# heart-shaped-smd-light-gift.net
KiCad netlist of a schematic drawn in EAGLE
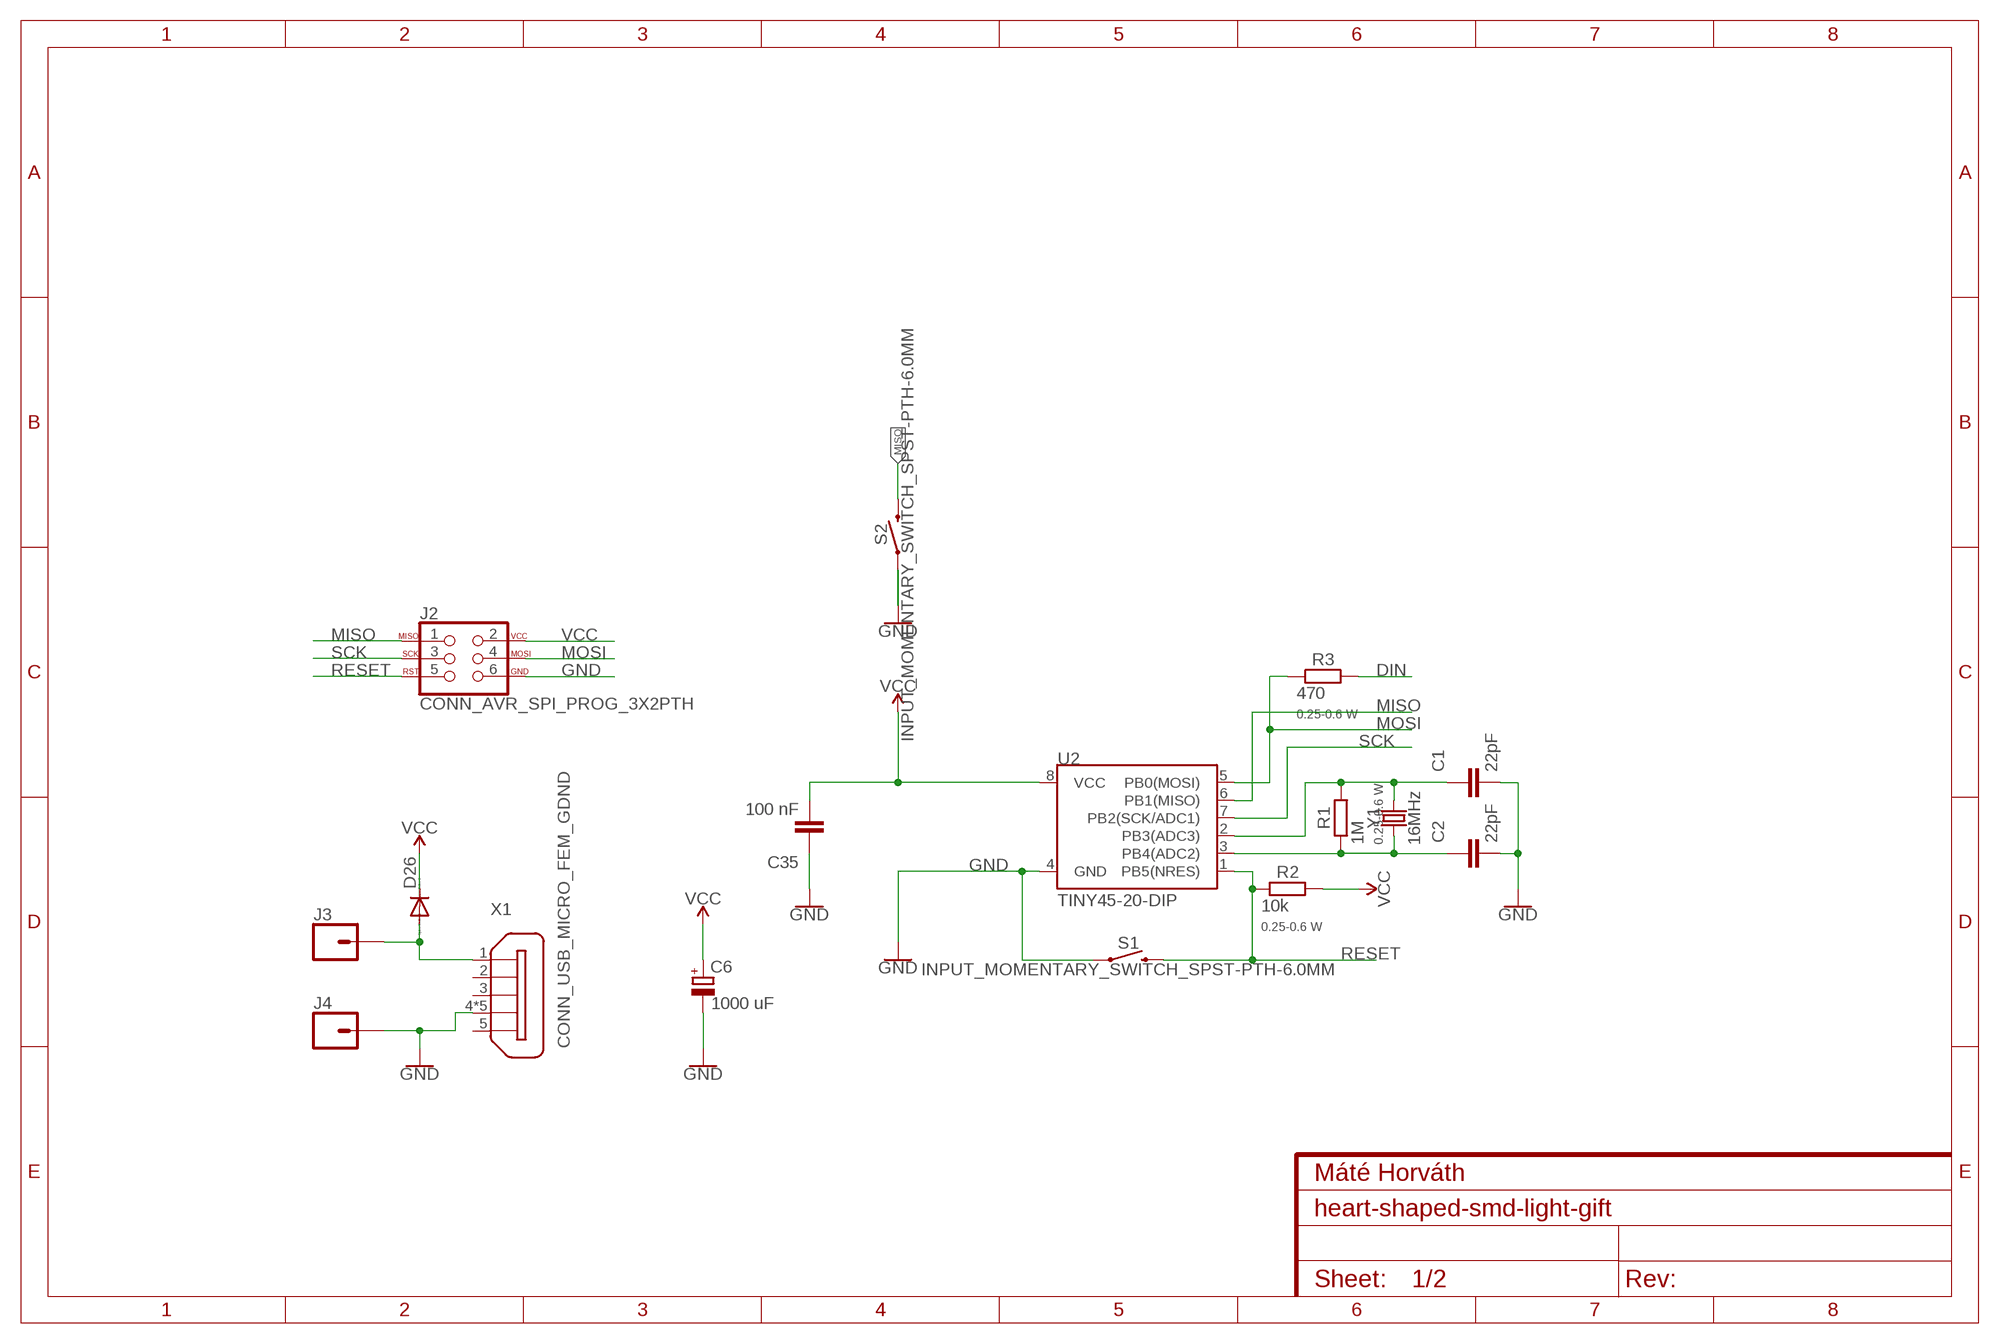
[diagram p0: schematic, sheet 1]
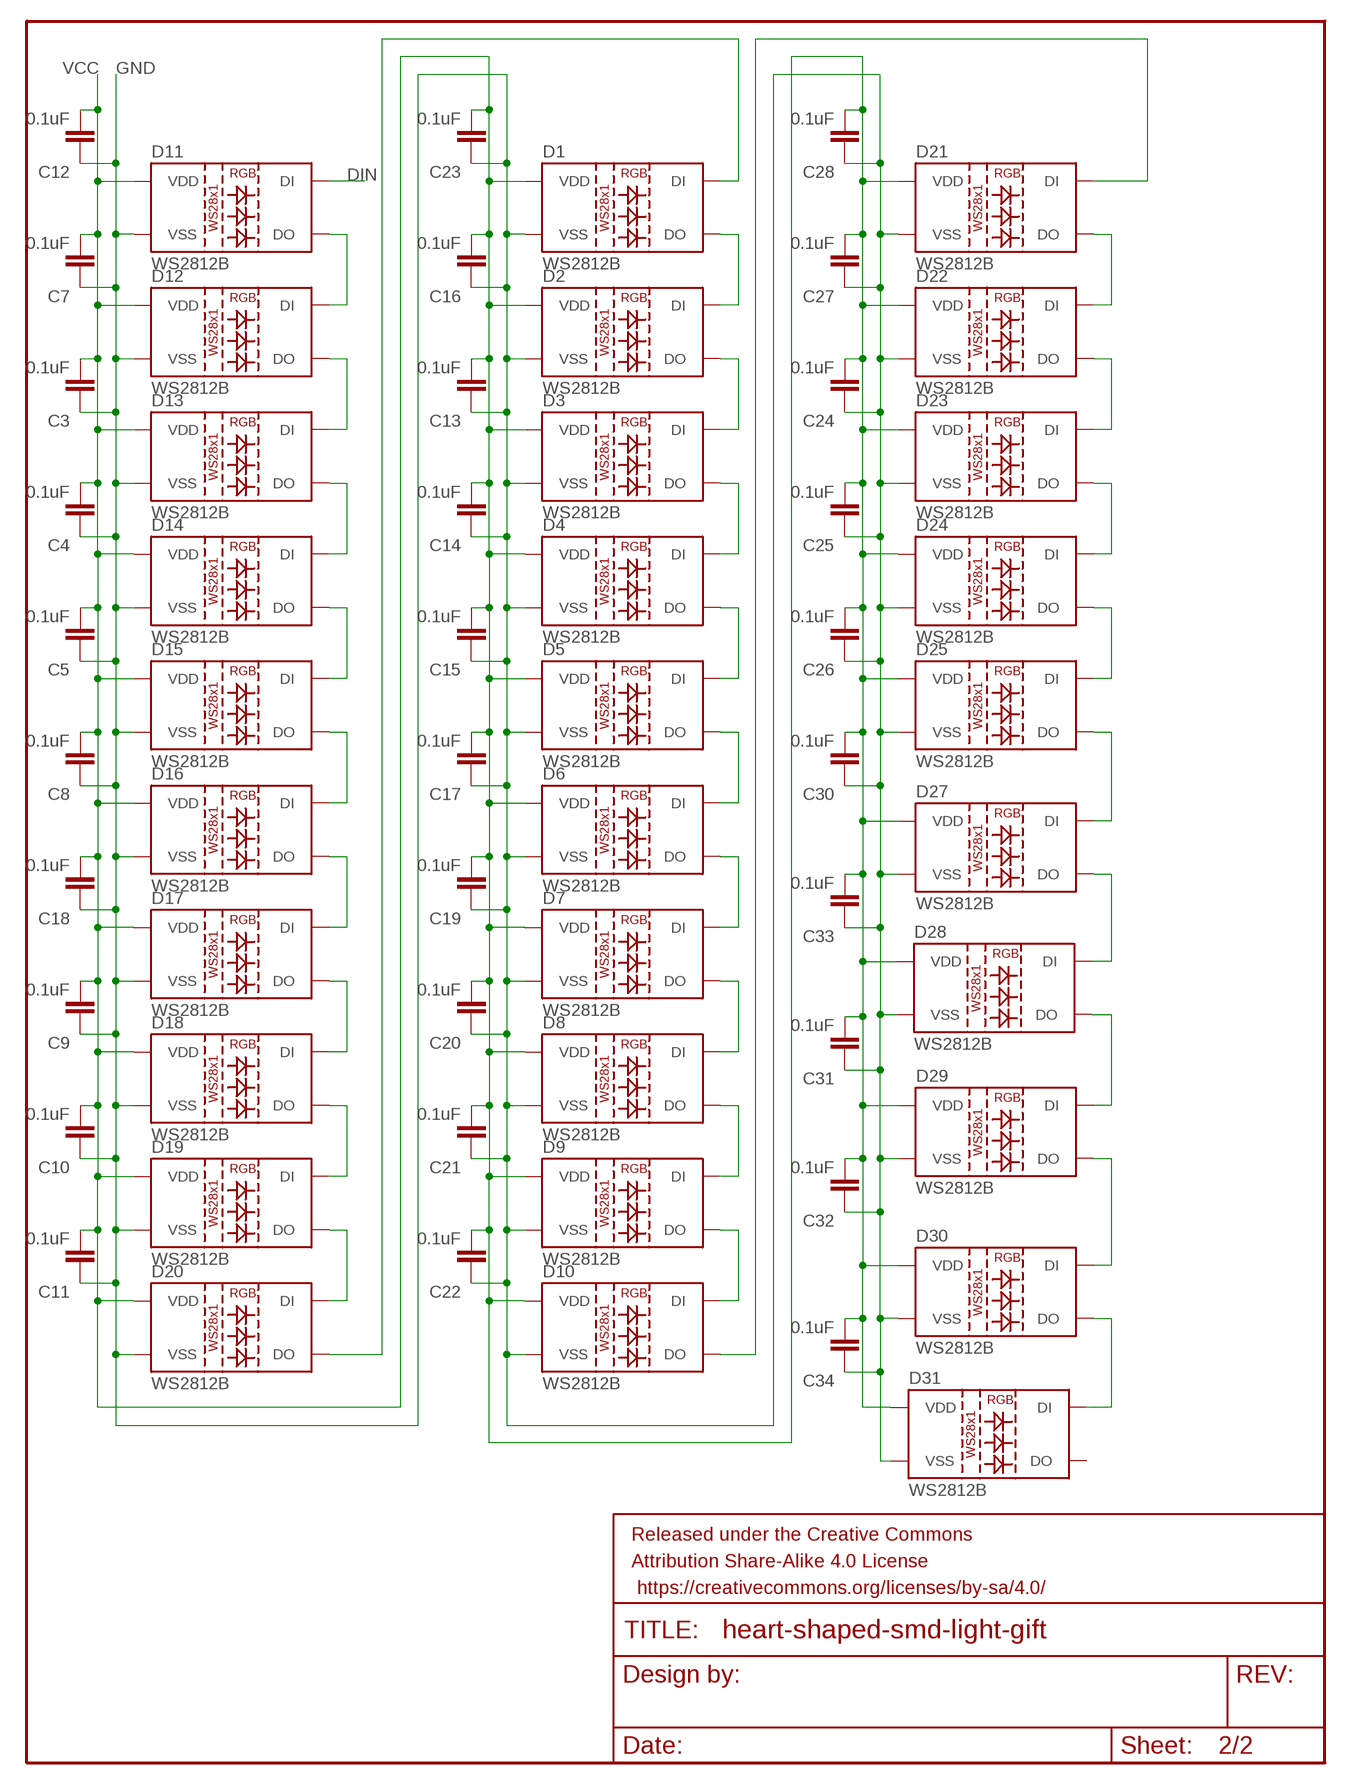
[diagram p1: schematic, sheet 2]

(export (version "E")
  (design (tool "Eeschema 10.0.6"))
  (components
    (comp (ref "C3")
      (value "0.1uF")
      (footprint "eagle-import:C1206I-C3216M")
      (libsource (lib "eagle-import") (part "CAPACITOR_1C1206"))
    )
    (comp (ref "C4")
      (value "0.1uF")
      (footprint "eagle-import:C1206I-C3216M")
      (libsource (lib "eagle-import") (part "CAPACITOR_1C1206"))
    )
    (comp (ref "C5")
      (value "0.1uF")
      (footprint "eagle-import:C1206I-C3216M")
      (libsource (lib "eagle-import") (part "CAPACITOR_1C1206"))
    )
    (comp (ref "C7")
      (value "0.1uF")
      (footprint "eagle-import:C1206I-C3216M")
      (libsource (lib "eagle-import") (part "CAPACITOR_1C1206"))
    )
    (comp (ref "C8")
      (value "0.1uF")
      (footprint "eagle-import:C1206I-C3216M")
      (libsource (lib "eagle-import") (part "CAPACITOR_1C1206"))
    )
    (comp (ref "C9")
      (value "0.1uF")
      (footprint "eagle-import:C1206I-C3216M")
      (libsource (lib "eagle-import") (part "CAPACITOR_1C1206"))
    )
    (comp (ref "C10")
      (value "0.1uF")
      (footprint "eagle-import:C1206I-C3216M")
      (libsource (lib "eagle-import") (part "CAPACITOR_1C1206"))
    )
    (comp (ref "C11")
      (value "0.1uF")
      (footprint "eagle-import:C1206I-C3216M")
      (libsource (lib "eagle-import") (part "CAPACITOR_1C1206"))
    )
    (comp (ref "C12")
      (value "0.1uF")
      (footprint "eagle-import:C1206I-C3216M")
      (libsource (lib "eagle-import") (part "CAPACITOR_1C1206"))
    )
    (comp (ref "C13")
      (value "0.1uF")
      (footprint "eagle-import:C1206I-C3216M")
      (libsource (lib "eagle-import") (part "CAPACITOR_1C1206"))
    )
    (comp (ref "C14")
      (value "0.1uF")
      (footprint "eagle-import:C1206I-C3216M")
      (libsource (lib "eagle-import") (part "CAPACITOR_1C1206"))
    )
    (comp (ref "C15")
      (value "0.1uF")
      (footprint "eagle-import:C1206I-C3216M")
      (libsource (lib "eagle-import") (part "CAPACITOR_1C1206"))
    )
    (comp (ref "C16")
      (value "0.1uF")
      (footprint "eagle-import:C1206I-C3216M")
      (libsource (lib "eagle-import") (part "CAPACITOR_1C1206"))
    )
    (comp (ref "C17")
      (value "0.1uF")
      (footprint "eagle-import:C1206I-C3216M")
      (libsource (lib "eagle-import") (part "CAPACITOR_1C1206"))
    )
    (comp (ref "C18")
      (value "0.1uF")
      (footprint "eagle-import:C1206I-C3216M")
      (libsource (lib "eagle-import") (part "CAPACITOR_1C1206"))
    )
    (comp (ref "C19")
      (value "0.1uF")
      (footprint "eagle-import:C1206I-C3216M")
      (libsource (lib "eagle-import") (part "CAPACITOR_1C1206"))
    )
    (comp (ref "C20")
      (value "0.1uF")
      (footprint "eagle-import:C1206I-C3216M")
      (libsource (lib "eagle-import") (part "CAPACITOR_1C1206"))
    )
    (comp (ref "C21")
      (value "0.1uF")
      (footprint "eagle-import:C1206I-C3216M")
      (libsource (lib "eagle-import") (part "CAPACITOR_1C1206"))
    )
    (comp (ref "C22")
      (value "0.1uF")
      (footprint "eagle-import:C1206I-C3216M")
      (libsource (lib "eagle-import") (part "CAPACITOR_1C1206"))
    )
    (comp (ref "C23")
      (value "0.1uF")
      (footprint "eagle-import:C1206I-C3216M")
      (libsource (lib "eagle-import") (part "CAPACITOR_1C1206"))
    )
    (comp (ref "C24")
      (value "0.1uF")
      (footprint "eagle-import:C1206I-C3216M")
      (libsource (lib "eagle-import") (part "CAPACITOR_1C1206"))
    )
    (comp (ref "C25")
      (value "0.1uF")
      (footprint "eagle-import:C1206I-C3216M")
      (libsource (lib "eagle-import") (part "CAPACITOR_1C1206"))
    )
    (comp (ref "C26")
      (value "0.1uF")
      (footprint "eagle-import:C1206I-C3216M")
      (libsource (lib "eagle-import") (part "CAPACITOR_1C1206"))
    )
    (comp (ref "C27")
      (value "0.1uF")
      (footprint "eagle-import:C1206I-C3216M")
      (libsource (lib "eagle-import") (part "CAPACITOR_1C1206"))
    )
    (comp (ref "C28")
      (value "0.1uF")
      (footprint "eagle-import:C1206I-C3216M")
      (libsource (lib "eagle-import") (part "CAPACITOR_1C1206"))
    )
    (comp (ref "C30")
      (value "0.1uF")
      (footprint "eagle-import:C1206I-C3216M")
      (libsource (lib "eagle-import") (part "CAPACITOR_1C1206"))
    )
    (comp (ref "C31")
      (value "0.1uF")
      (footprint "eagle-import:C1206I-C3216M")
      (libsource (lib "eagle-import") (part "CAPACITOR_1C1206"))
    )
    (comp (ref "C32")
      (value "0.1uF")
      (footprint "eagle-import:C1206I-C3216M")
      (libsource (lib "eagle-import") (part "CAPACITOR_1C1206"))
    )
    (comp (ref "C33")
      (value "0.1uF")
      (footprint "eagle-import:C1206I-C3216M")
      (libsource (lib "eagle-import") (part "CAPACITOR_1C1206"))
    )
    (comp (ref "C34")
      (value "0.1uF")
      (footprint "eagle-import:C1206I-C3216M")
      (libsource (lib "eagle-import") (part "CAPACITOR_1C1206"))
    )
    (comp (ref "D1")
      (value "WS2812B")
      (footprint "eagle-import:WS2812B")
      (libsource (lib "eagle-import") (part "LED_SMD_RGB_WS2812B"))
    )
    (comp (ref "D2")
      (value "WS2812B")
      (footprint "eagle-import:WS2812B")
      (libsource (lib "eagle-import") (part "LED_SMD_RGB_WS2812B"))
    )
    (comp (ref "D3")
      (value "WS2812B")
      (footprint "eagle-import:WS2812B")
      (libsource (lib "eagle-import") (part "LED_SMD_RGB_WS2812B"))
    )
    (comp (ref "D4")
      (value "WS2812B")
      (footprint "eagle-import:WS2812B")
      (libsource (lib "eagle-import") (part "LED_SMD_RGB_WS2812B"))
    )
    (comp (ref "D5")
      (value "WS2812B")
      (footprint "eagle-import:WS2812B")
      (libsource (lib "eagle-import") (part "LED_SMD_RGB_WS2812B"))
    )
    (comp (ref "D6")
      (value "WS2812B")
      (footprint "eagle-import:WS2812B")
      (libsource (lib "eagle-import") (part "LED_SMD_RGB_WS2812B"))
    )
    (comp (ref "D7")
      (value "WS2812B")
      (footprint "eagle-import:WS2812B")
      (libsource (lib "eagle-import") (part "LED_SMD_RGB_WS2812B"))
    )
    (comp (ref "D8")
      (value "WS2812B")
      (footprint "eagle-import:WS2812B")
      (libsource (lib "eagle-import") (part "LED_SMD_RGB_WS2812B"))
    )
    (comp (ref "D9")
      (value "WS2812B")
      (footprint "eagle-import:WS2812B")
      (libsource (lib "eagle-import") (part "LED_SMD_RGB_WS2812B"))
    )
    (comp (ref "D10")
      (value "WS2812B")
      (footprint "eagle-import:WS2812B")
      (libsource (lib "eagle-import") (part "LED_SMD_RGB_WS2812B"))
    )
    (comp (ref "D11")
      (value "WS2812B")
      (footprint "eagle-import:WS2812B")
      (libsource (lib "eagle-import") (part "LED_SMD_RGB_WS2812B"))
    )
    (comp (ref "D12")
      (value "WS2812B")
      (footprint "eagle-import:WS2812B")
      (libsource (lib "eagle-import") (part "LED_SMD_RGB_WS2812B"))
    )
    (comp (ref "D13")
      (value "WS2812B")
      (footprint "eagle-import:WS2812B")
      (libsource (lib "eagle-import") (part "LED_SMD_RGB_WS2812B"))
    )
    (comp (ref "D14")
      (value "WS2812B")
      (footprint "eagle-import:WS2812B")
      (libsource (lib "eagle-import") (part "LED_SMD_RGB_WS2812B"))
    )
    (comp (ref "D15")
      (value "WS2812B")
      (footprint "eagle-import:WS2812B")
      (libsource (lib "eagle-import") (part "LED_SMD_RGB_WS2812B"))
    )
    (comp (ref "D16")
      (value "WS2812B")
      (footprint "eagle-import:WS2812B")
      (libsource (lib "eagle-import") (part "LED_SMD_RGB_WS2812B"))
    )
    (comp (ref "D17")
      (value "WS2812B")
      (footprint "eagle-import:WS2812B")
      (libsource (lib "eagle-import") (part "LED_SMD_RGB_WS2812B"))
    )
    (comp (ref "D18")
      (value "WS2812B")
      (footprint "eagle-import:WS2812B")
      (libsource (lib "eagle-import") (part "LED_SMD_RGB_WS2812B"))
    )
    (comp (ref "D19")
      (value "WS2812B")
      (footprint "eagle-import:WS2812B")
      (libsource (lib "eagle-import") (part "LED_SMD_RGB_WS2812B"))
    )
    (comp (ref "D20")
      (value "WS2812B")
      (footprint "eagle-import:WS2812B")
      (libsource (lib "eagle-import") (part "LED_SMD_RGB_WS2812B"))
    )
    (comp (ref "D21")
      (value "WS2812B")
      (footprint "eagle-import:WS2812B")
      (libsource (lib "eagle-import") (part "LED_SMD_RGB_WS2812B"))
    )
    (comp (ref "D22")
      (value "WS2812B")
      (footprint "eagle-import:WS2812B")
      (libsource (lib "eagle-import") (part "LED_SMD_RGB_WS2812B"))
    )
    (comp (ref "D23")
      (value "WS2812B")
      (footprint "eagle-import:WS2812B")
      (libsource (lib "eagle-import") (part "LED_SMD_RGB_WS2812B"))
    )
    (comp (ref "D24")
      (value "WS2812B")
      (footprint "eagle-import:WS2812B")
      (libsource (lib "eagle-import") (part "LED_SMD_RGB_WS2812B"))
    )
    (comp (ref "D25")
      (value "WS2812B")
      (footprint "eagle-import:WS2812B")
      (libsource (lib "eagle-import") (part "LED_SMD_RGB_WS2812B"))
    )
    (comp (ref "D27")
      (value "WS2812B")
      (footprint "eagle-import:WS2812B")
      (libsource (lib "eagle-import") (part "LED_SMD_RGB_WS2812B"))
    )
    (comp (ref "D28")
      (value "WS2812B")
      (footprint "eagle-import:WS2812B")
      (libsource (lib "eagle-import") (part "LED_SMD_RGB_WS2812B"))
    )
    (comp (ref "D29")
      (value "WS2812B")
      (footprint "eagle-import:WS2812B")
      (libsource (lib "eagle-import") (part "LED_SMD_RGB_WS2812B"))
    )
    (comp (ref "D30")
      (value "WS2812B")
      (footprint "eagle-import:WS2812B")
      (libsource (lib "eagle-import") (part "LED_SMD_RGB_WS2812B"))
    )
    (comp (ref "D31")
      (value "WS2812B")
      (footprint "eagle-import:WS2812B")
      (libsource (lib "eagle-import") (part "LED_SMD_RGB_WS2812B"))
    )
    (comp (ref "FRAME2")
      (value "FRAME_LETTERNO_PACKAGE")
      (footprint "eagle-import:DUMMY")
      (fields (field (name "DESIGNER") "Nobody"))
      (libsource (lib "eagle-import") (part "FRAME_LETTERNO_PACKAGE"))
    )
    (comp (ref "C1")
      (value "22pF")
      (footprint "eagle-import:C1206I-C3216M")
      (libsource (lib "eagle-import") (part "CAPACITOR_1C1206"))
    )
    (comp (ref "C2")
      (value "22pF")
      (footprint "eagle-import:C1206I-C3216M")
      (libsource (lib "eagle-import") (part "CAPACITOR_1C1206"))
    )
    (comp (ref "C6")
      (value "1000 uF")
      (footprint "eagle-import:153CLV-1010")
      (libsource (lib "eagle-import") (part "CAPACITOR_POLARIZED153CLV-1010"))
    )
    (comp (ref "C35")
      (value "100 nF")
      (footprint "eagle-import:C1206I-C3216M")
      (libsource (lib "eagle-import") (part "CAPACITOR_1C1206"))
    )
    (comp (ref "D26")
      (value "DIODED-7.5")
      (footprint "eagle-import:D-7.5")
      (libsource (lib "eagle-import") (part "DIODED-7.5"))
    )
    (comp (ref "J2")
      (value "CONN_AVR_SPI_PROG_3X2PTH")
      (footprint "eagle-import:2X3_S")
      (libsource (lib "eagle-import") (part "CONN_AVR_SPI_PROG_3X2PTH"))
    )
    (comp (ref "J3")
      (value "CONN_01SNAP-MALE")
      (footprint "eagle-import:SNAP-MALE")
      (libsource (lib "eagle-import") (part "CONN_01SNAP-MALE"))
    )
    (comp (ref "J4")
      (value "CONN_01SNAP-MALE")
      (footprint "eagle-import:SNAP-MALE")
      (libsource (lib "eagle-import") (part "CONN_01SNAP-MALE"))
    )
    (comp (ref "R1")
      (value "1M")
      (footprint "eagle-import:0207_7")
      (fields (field (name "POWER") "0.25-0.6 W"))
      (libsource (lib "eagle-import") (part "RESISTOR0207/7"))
    )
    (comp (ref "R2")
      (value "10k")
      (footprint "eagle-import:0207_7")
      (fields (field (name "POWER") "0.25-0.6 W"))
      (libsource (lib "eagle-import") (part "RESISTOR0207/7"))
    )
    (comp (ref "R3")
      (value "470")
      (footprint "eagle-import:0207_7")
      (fields (field (name "POWER") "0.25-0.6 W"))
      (libsource (lib "eagle-import") (part "RESISTOR0207/7"))
    )
    (comp (ref "S1")
      (value "INPUT_MOMENTARY_SWITCH_SPST-PTH-6.0MM")
      (footprint "eagle-import:TACTILE_SWITCH_PTH_6.0MM")
      (libsource (lib "eagle-import") (part "INPUT_MOMENTARY_SWITCH_SPST-PTH-6.0MM"))
    )
    (comp (ref "S2")
      (value "INPUT_MOMENTARY_SWITCH_SPST-PTH-6.0MM")
      (footprint "eagle-import:TACTILE_SWITCH_PTH_6.0MM")
      (libsource (lib "eagle-import") (part "INPUT_MOMENTARY_SWITCH_SPST-PTH-6.0MM"))
    )
    (comp (ref "U2")
      (value "TINY45-20-DIP")
      (footprint "eagle-import:DIP08")
      (libsource (lib "eagle-import") (part "MCU_ATTINY45TINY45-20-DIP"))
    )
    (comp (ref "X1")
      (value "CONN_USB_MICRO_FEM_GDND")
      (footprint "eagle-import:ZX62D-B-5PA8")
      (fields (field (name "MF") "Hirose") (field (name "MPN") "ZX62D-B-5PA8"))
      (libsource (lib "eagle-import") (part "CONN_USB_MICRO_FEM_GDND"))
    )
    (comp (ref "Y1")
      (value "16MHz")
      (footprint "eagle-import:HC49US")
      (libsource (lib "eagle-import") (part "CRYSTALPTH-HC49US"))
    )
  )
  (nets
    (net (code "1") (name "DIN") (class "Default")
      (node (ref "D11") (pin "4") (pinfunction "DI_4") (pintype "bidirectional"))
      (node (ref "R3") (pin "2") (pinfunction "2_2") (pintype "passive"))
    )
    (net (code "2") (name "GND") (class "Default")
      (node (ref "C1") (pin "2") (pinfunction "2_2") (pintype "passive"))
      (node (ref "C10") (pin "1") (pinfunction "1_1") (pintype "passive"))
      (node (ref "C11") (pin "1") (pinfunction "1_1") (pintype "passive"))
      (node (ref "C12") (pin "1") (pinfunction "1_1") (pintype "passive"))
      (node (ref "C13") (pin "1") (pinfunction "1_1") (pintype "passive"))
      (node (ref "C14") (pin "1") (pinfunction "1_1") (pintype "passive"))
      (node (ref "C15") (pin "1") (pinfunction "1_1") (pintype "passive"))
      (node (ref "C16") (pin "1") (pinfunction "1_1") (pintype "passive"))
      (node (ref "C17") (pin "1") (pinfunction "1_1") (pintype "passive"))
      (node (ref "C18") (pin "1") (pinfunction "1_1") (pintype "passive"))
      (node (ref "C19") (pin "1") (pinfunction "1_1") (pintype "passive"))
      (node (ref "C2") (pin "2") (pinfunction "2_2") (pintype "passive"))
      (node (ref "C20") (pin "1") (pinfunction "1_1") (pintype "passive"))
      (node (ref "C21") (pin "1") (pinfunction "1_1") (pintype "passive"))
      (node (ref "C22") (pin "1") (pinfunction "1_1") (pintype "passive"))
      (node (ref "C23") (pin "1") (pinfunction "1_1") (pintype "passive"))
      (node (ref "C24") (pin "1") (pinfunction "1_1") (pintype "passive"))
      (node (ref "C25") (pin "1") (pinfunction "1_1") (pintype "passive"))
      (node (ref "C26") (pin "1") (pinfunction "1_1") (pintype "passive"))
      (node (ref "C27") (pin "1") (pinfunction "1_1") (pintype "passive"))
      (node (ref "C28") (pin "1") (pinfunction "1_1") (pintype "passive"))
      (node (ref "C3") (pin "1") (pinfunction "1_1") (pintype "passive"))
      (node (ref "C30") (pin "1") (pinfunction "1_1") (pintype "passive"))
      (node (ref "C31") (pin "1") (pinfunction "1_1") (pintype "passive"))
      (node (ref "C32") (pin "1") (pinfunction "1_1") (pintype "passive"))
      (node (ref "C33") (pin "1") (pinfunction "1_1") (pintype "passive"))
      (node (ref "C34") (pin "1") (pinfunction "1_1") (pintype "passive"))
      (node (ref "C35") (pin "1") (pinfunction "1_1") (pintype "passive"))
      (node (ref "C4") (pin "1") (pinfunction "1_1") (pintype "passive"))
      (node (ref "C5") (pin "1") (pinfunction "1_1") (pintype "passive"))
      (node (ref "C6") (pin "-") (pinfunction "-_-") (pintype "passive"))
      (node (ref "C7") (pin "1") (pinfunction "1_1") (pintype "passive"))
      (node (ref "C8") (pin "1") (pinfunction "1_1") (pintype "passive"))
      (node (ref "C9") (pin "1") (pinfunction "1_1") (pintype "passive"))
      (node (ref "D1") (pin "3") (pinfunction "VSS_3") (pintype "bidirectional"))
      (node (ref "D10") (pin "3") (pinfunction "VSS_3") (pintype "bidirectional"))
      (node (ref "D11") (pin "3") (pinfunction "VSS_3") (pintype "bidirectional"))
      (node (ref "D12") (pin "3") (pinfunction "VSS_3") (pintype "bidirectional"))
      (node (ref "D13") (pin "3") (pinfunction "VSS_3") (pintype "bidirectional"))
      (node (ref "D14") (pin "3") (pinfunction "VSS_3") (pintype "bidirectional"))
      (node (ref "D15") (pin "3") (pinfunction "VSS_3") (pintype "bidirectional"))
      (node (ref "D16") (pin "3") (pinfunction "VSS_3") (pintype "bidirectional"))
      (node (ref "D17") (pin "3") (pinfunction "VSS_3") (pintype "bidirectional"))
      (node (ref "D18") (pin "3") (pinfunction "VSS_3") (pintype "bidirectional"))
      (node (ref "D19") (pin "3") (pinfunction "VSS_3") (pintype "bidirectional"))
      (node (ref "D2") (pin "3") (pinfunction "VSS_3") (pintype "bidirectional"))
      (node (ref "D20") (pin "3") (pinfunction "VSS_3") (pintype "bidirectional"))
      (node (ref "D21") (pin "3") (pinfunction "VSS_3") (pintype "bidirectional"))
      (node (ref "D22") (pin "3") (pinfunction "VSS_3") (pintype "bidirectional"))
      (node (ref "D23") (pin "3") (pinfunction "VSS_3") (pintype "bidirectional"))
      (node (ref "D24") (pin "3") (pinfunction "VSS_3") (pintype "bidirectional"))
      (node (ref "D25") (pin "3") (pinfunction "VSS_3") (pintype "bidirectional"))
      (node (ref "D27") (pin "3") (pinfunction "VSS_3") (pintype "bidirectional"))
      (node (ref "D28") (pin "3") (pinfunction "VSS_3") (pintype "bidirectional"))
      (node (ref "D29") (pin "3") (pinfunction "VSS_3") (pintype "bidirectional"))
      (node (ref "D3") (pin "3") (pinfunction "VSS_3") (pintype "bidirectional"))
      (node (ref "D30") (pin "3") (pinfunction "VSS_3") (pintype "bidirectional"))
      (node (ref "D31") (pin "3") (pinfunction "VSS_3") (pintype "bidirectional"))
      (node (ref "D4") (pin "3") (pinfunction "VSS_3") (pintype "bidirectional"))
      (node (ref "D5") (pin "3") (pinfunction "VSS_3") (pintype "bidirectional"))
      (node (ref "D6") (pin "3") (pinfunction "VSS_3") (pintype "bidirectional"))
      (node (ref "D7") (pin "3") (pinfunction "VSS_3") (pintype "bidirectional"))
      (node (ref "D8") (pin "3") (pinfunction "VSS_3") (pintype "bidirectional"))
      (node (ref "D9") (pin "3") (pinfunction "VSS_3") (pintype "bidirectional"))
      (node (ref "J2") (pin "6") (pinfunction "6_6") (pintype "passive"))
      (node (ref "J4") (pin "2") (pinfunction "1_2") (pintype "passive"))
      (node (ref "S1") (pin "1") (pinfunction "1_1") (pintype "passive"))
      (node (ref "S2") (pin "1") (pinfunction "1_1") (pintype "passive"))
      (node (ref "U2") (pin "4") (pinfunction "GND_4") (pintype "bidirectional"))
      (node (ref "X1") (pin "4") (pinfunction "4_4") (pintype "passive"))
      (node (ref "X1") (pin "S1") (pinfunction "4_S1") (pintype "passive"))
      (node (ref "X1") (pin "S2") (pinfunction "4_S2") (pintype "passive"))
      (node (ref "X1") (pin "S3") (pinfunction "4_S3") (pintype "passive"))
      (node (ref "X1") (pin "S4") (pinfunction "4_S4") (pintype "passive"))
    )
    (net (code "3") (name "MISO") (class "Default")
      (node (ref "J2") (pin "1") (pinfunction "1_1") (pintype "passive"))
      (node (ref "S2") (pin "3") (pinfunction "2_3") (pintype "passive"))
      (node (ref "U2") (pin "6") (pinfunction "PB1(MISO)_6") (pintype "bidirectional"))
    )
    (net (code "4") (name "MOSI") (class "Default")
      (node (ref "J2") (pin "4") (pinfunction "4_4") (pintype "passive"))
      (node (ref "R3") (pin "1") (pinfunction "1_1") (pintype "passive"))
      (node (ref "U2") (pin "5") (pinfunction "PB0(MOSI)_5") (pintype "bidirectional"))
    )
    (net (code "5") (name "Net-(D1-DI)") (class "Default")
      (node (ref "D1") (pin "4") (pinfunction "DI_4") (pintype "bidirectional"))
      (node (ref "D20") (pin "2") (pinfunction "DO_2") (pintype "bidirectional"))
    )
    (net (code "6") (name "Net-(D1-DO)") (class "Default")
      (node (ref "D1") (pin "2") (pinfunction "DO_2") (pintype "bidirectional"))
      (node (ref "D2") (pin "4") (pinfunction "DI_4") (pintype "bidirectional"))
    )
    (net (code "7") (name "Net-(D2-DO)") (class "Default")
      (node (ref "D2") (pin "2") (pinfunction "DO_2") (pintype "bidirectional"))
      (node (ref "D3") (pin "4") (pinfunction "DI_4") (pintype "bidirectional"))
    )
    (net (code "8") (name "Net-(D3-DO)") (class "Default")
      (node (ref "D3") (pin "2") (pinfunction "DO_2") (pintype "bidirectional"))
      (node (ref "D4") (pin "4") (pinfunction "DI_4") (pintype "bidirectional"))
    )
    (net (code "9") (name "Net-(D4-DO)") (class "Default")
      (node (ref "D4") (pin "2") (pinfunction "DO_2") (pintype "bidirectional"))
      (node (ref "D5") (pin "4") (pinfunction "DI_4") (pintype "bidirectional"))
    )
    (net (code "10") (name "Net-(D5-DO)") (class "Default")
      (node (ref "D5") (pin "2") (pinfunction "DO_2") (pintype "bidirectional"))
      (node (ref "D6") (pin "4") (pinfunction "DI_4") (pintype "bidirectional"))
    )
    (net (code "11") (name "Net-(D6-DO)") (class "Default")
      (node (ref "D6") (pin "2") (pinfunction "DO_2") (pintype "bidirectional"))
      (node (ref "D7") (pin "4") (pinfunction "DI_4") (pintype "bidirectional"))
    )
    (net (code "12") (name "Net-(D7-DO)") (class "Default")
      (node (ref "D7") (pin "2") (pinfunction "DO_2") (pintype "bidirectional"))
      (node (ref "D8") (pin "4") (pinfunction "DI_4") (pintype "bidirectional"))
    )
    (net (code "13") (name "Net-(D8-DO)") (class "Default")
      (node (ref "D8") (pin "2") (pinfunction "DO_2") (pintype "bidirectional"))
      (node (ref "D9") (pin "4") (pinfunction "DI_4") (pintype "bidirectional"))
    )
    (net (code "14") (name "Net-(D10-DI)") (class "Default")
      (node (ref "D10") (pin "4") (pinfunction "DI_4") (pintype "bidirectional"))
      (node (ref "D9") (pin "2") (pinfunction "DO_2") (pintype "bidirectional"))
    )
    (net (code "15") (name "Net-(D10-DO)") (class "Default")
      (node (ref "D10") (pin "2") (pinfunction "DO_2") (pintype "bidirectional"))
      (node (ref "D21") (pin "4") (pinfunction "DI_4") (pintype "bidirectional"))
    )
    (net (code "16") (name "Net-(D11-DO)") (class "Default")
      (node (ref "D11") (pin "2") (pinfunction "DO_2") (pintype "bidirectional"))
      (node (ref "D12") (pin "4") (pinfunction "DI_4") (pintype "bidirectional"))
    )
    (net (code "17") (name "Net-(D12-DO)") (class "Default")
      (node (ref "D12") (pin "2") (pinfunction "DO_2") (pintype "bidirectional"))
      (node (ref "D13") (pin "4") (pinfunction "DI_4") (pintype "bidirectional"))
    )
    (net (code "18") (name "Net-(D13-DO)") (class "Default")
      (node (ref "D13") (pin "2") (pinfunction "DO_2") (pintype "bidirectional"))
      (node (ref "D14") (pin "4") (pinfunction "DI_4") (pintype "bidirectional"))
    )
    (net (code "19") (name "Net-(D14-DO)") (class "Default")
      (node (ref "D14") (pin "2") (pinfunction "DO_2") (pintype "bidirectional"))
      (node (ref "D15") (pin "4") (pinfunction "DI_4") (pintype "bidirectional"))
    )
    (net (code "20") (name "Net-(D15-DO)") (class "Default")
      (node (ref "D15") (pin "2") (pinfunction "DO_2") (pintype "bidirectional"))
      (node (ref "D16") (pin "4") (pinfunction "DI_4") (pintype "bidirectional"))
    )
    (net (code "21") (name "Net-(D16-DO)") (class "Default")
      (node (ref "D16") (pin "2") (pinfunction "DO_2") (pintype "bidirectional"))
      (node (ref "D17") (pin "4") (pinfunction "DI_4") (pintype "bidirectional"))
    )
    (net (code "22") (name "Net-(D17-DO)") (class "Default")
      (node (ref "D17") (pin "2") (pinfunction "DO_2") (pintype "bidirectional"))
      (node (ref "D18") (pin "4") (pinfunction "DI_4") (pintype "bidirectional"))
    )
    (net (code "23") (name "Net-(D18-DO)") (class "Default")
      (node (ref "D18") (pin "2") (pinfunction "DO_2") (pintype "bidirectional"))
      (node (ref "D19") (pin "4") (pinfunction "DI_4") (pintype "bidirectional"))
    )
    (net (code "24") (name "Net-(D19-DO)") (class "Default")
      (node (ref "D19") (pin "2") (pinfunction "DO_2") (pintype "bidirectional"))
      (node (ref "D20") (pin "4") (pinfunction "DI_4") (pintype "bidirectional"))
    )
    (net (code "25") (name "Net-(D21-DO)") (class "Default")
      (node (ref "D21") (pin "2") (pinfunction "DO_2") (pintype "bidirectional"))
      (node (ref "D22") (pin "4") (pinfunction "DI_4") (pintype "bidirectional"))
    )
    (net (code "26") (name "Net-(D22-DO)") (class "Default")
      (node (ref "D22") (pin "2") (pinfunction "DO_2") (pintype "bidirectional"))
      (node (ref "D23") (pin "4") (pinfunction "DI_4") (pintype "bidirectional"))
    )
    (net (code "27") (name "Net-(D23-DO)") (class "Default")
      (node (ref "D23") (pin "2") (pinfunction "DO_2") (pintype "bidirectional"))
      (node (ref "D24") (pin "4") (pinfunction "DI_4") (pintype "bidirectional"))
    )
    (net (code "28") (name "Net-(D24-DO)") (class "Default")
      (node (ref "D24") (pin "2") (pinfunction "DO_2") (pintype "bidirectional"))
      (node (ref "D25") (pin "4") (pinfunction "DI_4") (pintype "bidirectional"))
    )
    (net (code "29") (name "Net-(D25-DO)") (class "Default")
      (node (ref "D25") (pin "2") (pinfunction "DO_2") (pintype "bidirectional"))
      (node (ref "D27") (pin "4") (pinfunction "DI_4") (pintype "bidirectional"))
    )
    (net (code "30") (name "Net-(D27-DO)") (class "Default")
      (node (ref "D27") (pin "2") (pinfunction "DO_2") (pintype "bidirectional"))
      (node (ref "D28") (pin "4") (pinfunction "DI_4") (pintype "bidirectional"))
    )
    (net (code "31") (name "Net-(D28-DO)") (class "Default")
      (node (ref "D28") (pin "2") (pinfunction "DO_2") (pintype "bidirectional"))
      (node (ref "D29") (pin "4") (pinfunction "DI_4") (pintype "bidirectional"))
    )
    (net (code "32") (name "Net-(D29-DO)") (class "Default")
      (node (ref "D29") (pin "2") (pinfunction "DO_2") (pintype "bidirectional"))
      (node (ref "D30") (pin "4") (pinfunction "DI_4") (pintype "bidirectional"))
    )
    (net (code "33") (name "Net-(D30-DO)") (class "Default")
      (node (ref "D30") (pin "2") (pinfunction "DO_2") (pintype "bidirectional"))
      (node (ref "D31") (pin "4") (pinfunction "DI_4") (pintype "bidirectional"))
    )
    (net (code "34") (name "Net-(J3-1)") (class "Default")
      (node (ref "D26") (pin "A") (pinfunction "A_A") (pintype "passive"))
      (node (ref "J3") (pin "2") (pinfunction "1_2") (pintype "passive"))
      (node (ref "X1") (pin "1") (pinfunction "1_1") (pintype "passive"))
    )
    (net (code "35") (name "Net-(U2-PB3(ADC3))") (class "Default")
      (node (ref "C1") (pin "1") (pinfunction "1_1") (pintype "passive"))
      (node (ref "R1") (pin "2") (pinfunction "2_2") (pintype "passive"))
      (node (ref "U2") (pin "2") (pinfunction "PB3(ADC3)_2") (pintype "bidirectional"))
      (node (ref "Y1") (pin "2") (pinfunction "2_2") (pintype "passive"))
    )
    (net (code "36") (name "Net-(U2-PB4(ADC2))") (class "Default")
      (node (ref "C2") (pin "1") (pinfunction "1_1") (pintype "passive"))
      (node (ref "R1") (pin "1") (pinfunction "1_1") (pintype "passive"))
      (node (ref "U2") (pin "3") (pinfunction "PB4(ADC2)_3") (pintype "bidirectional"))
      (node (ref "Y1") (pin "1") (pinfunction "1_1") (pintype "passive"))
    )
    (net (code "37") (name "RESET") (class "Default")
      (node (ref "J2") (pin "5") (pinfunction "5_5") (pintype "passive"))
      (node (ref "R2") (pin "1") (pinfunction "1_1") (pintype "passive"))
      (node (ref "S1") (pin "3") (pinfunction "2_3") (pintype "passive"))
      (node (ref "U2") (pin "1") (pinfunction "PB5(NRES)_1") (pintype "bidirectional"))
    )
    (net (code "38") (name "SCK") (class "Default")
      (node (ref "J2") (pin "3") (pinfunction "3_3") (pintype "passive"))
      (node (ref "U2") (pin "7") (pinfunction "PB2(SCK/ADC1)_7") (pintype "bidirectional"))
    )
    (net (code "39") (name "VCC") (class "Default")
      (node (ref "C10") (pin "2") (pinfunction "2_2") (pintype "passive"))
      (node (ref "C11") (pin "2") (pinfunction "2_2") (pintype "passive"))
      (node (ref "C12") (pin "2") (pinfunction "2_2") (pintype "passive"))
      (node (ref "C13") (pin "2") (pinfunction "2_2") (pintype "passive"))
      (node (ref "C14") (pin "2") (pinfunction "2_2") (pintype "passive"))
      (node (ref "C15") (pin "2") (pinfunction "2_2") (pintype "passive"))
      (node (ref "C16") (pin "2") (pinfunction "2_2") (pintype "passive"))
      (node (ref "C17") (pin "2") (pinfunction "2_2") (pintype "passive"))
      (node (ref "C18") (pin "2") (pinfunction "2_2") (pintype "passive"))
      (node (ref "C19") (pin "2") (pinfunction "2_2") (pintype "passive"))
      (node (ref "C20") (pin "2") (pinfunction "2_2") (pintype "passive"))
      (node (ref "C21") (pin "2") (pinfunction "2_2") (pintype "passive"))
      (node (ref "C22") (pin "2") (pinfunction "2_2") (pintype "passive"))
      (node (ref "C23") (pin "2") (pinfunction "2_2") (pintype "passive"))
      (node (ref "C24") (pin "2") (pinfunction "2_2") (pintype "passive"))
      (node (ref "C25") (pin "2") (pinfunction "2_2") (pintype "passive"))
      (node (ref "C26") (pin "2") (pinfunction "2_2") (pintype "passive"))
      (node (ref "C27") (pin "2") (pinfunction "2_2") (pintype "passive"))
      (node (ref "C28") (pin "2") (pinfunction "2_2") (pintype "passive"))
      (node (ref "C3") (pin "2") (pinfunction "2_2") (pintype "passive"))
      (node (ref "C30") (pin "2") (pinfunction "2_2") (pintype "passive"))
      (node (ref "C31") (pin "2") (pinfunction "2_2") (pintype "passive"))
      (node (ref "C32") (pin "2") (pinfunction "2_2") (pintype "passive"))
      (node (ref "C33") (pin "2") (pinfunction "2_2") (pintype "passive"))
      (node (ref "C34") (pin "2") (pinfunction "2_2") (pintype "passive"))
      (node (ref "C35") (pin "2") (pinfunction "2_2") (pintype "passive"))
      (node (ref "C4") (pin "2") (pinfunction "2_2") (pintype "passive"))
      (node (ref "C5") (pin "2") (pinfunction "2_2") (pintype "passive"))
      (node (ref "C6") (pin "+") (pinfunction "+_+") (pintype "passive"))
      (node (ref "C7") (pin "2") (pinfunction "2_2") (pintype "passive"))
      (node (ref "C8") (pin "2") (pinfunction "2_2") (pintype "passive"))
      (node (ref "C9") (pin "2") (pinfunction "2_2") (pintype "passive"))
      (node (ref "D1") (pin "1") (pinfunction "VDD_1") (pintype "bidirectional"))
      (node (ref "D10") (pin "1") (pinfunction "VDD_1") (pintype "bidirectional"))
      (node (ref "D11") (pin "1") (pinfunction "VDD_1") (pintype "bidirectional"))
      (node (ref "D12") (pin "1") (pinfunction "VDD_1") (pintype "bidirectional"))
      (node (ref "D13") (pin "1") (pinfunction "VDD_1") (pintype "bidirectional"))
      (node (ref "D14") (pin "1") (pinfunction "VDD_1") (pintype "bidirectional"))
      (node (ref "D15") (pin "1") (pinfunction "VDD_1") (pintype "bidirectional"))
      (node (ref "D16") (pin "1") (pinfunction "VDD_1") (pintype "bidirectional"))
      (node (ref "D17") (pin "1") (pinfunction "VDD_1") (pintype "bidirectional"))
      (node (ref "D18") (pin "1") (pinfunction "VDD_1") (pintype "bidirectional"))
      (node (ref "D19") (pin "1") (pinfunction "VDD_1") (pintype "bidirectional"))
      (node (ref "D2") (pin "1") (pinfunction "VDD_1") (pintype "bidirectional"))
      (node (ref "D20") (pin "1") (pinfunction "VDD_1") (pintype "bidirectional"))
      (node (ref "D21") (pin "1") (pinfunction "VDD_1") (pintype "bidirectional"))
      (node (ref "D22") (pin "1") (pinfunction "VDD_1") (pintype "bidirectional"))
      (node (ref "D23") (pin "1") (pinfunction "VDD_1") (pintype "bidirectional"))
      (node (ref "D24") (pin "1") (pinfunction "VDD_1") (pintype "bidirectional"))
      (node (ref "D25") (pin "1") (pinfunction "VDD_1") (pintype "bidirectional"))
      (node (ref "D26") (pin "C") (pinfunction "C_C") (pintype "passive"))
      (node (ref "D27") (pin "1") (pinfunction "VDD_1") (pintype "bidirectional"))
      (node (ref "D28") (pin "1") (pinfunction "VDD_1") (pintype "bidirectional"))
      (node (ref "D29") (pin "1") (pinfunction "VDD_1") (pintype "bidirectional"))
      (node (ref "D3") (pin "1") (pinfunction "VDD_1") (pintype "bidirectional"))
      (node (ref "D30") (pin "1") (pinfunction "VDD_1") (pintype "bidirectional"))
      (node (ref "D31") (pin "1") (pinfunction "VDD_1") (pintype "bidirectional"))
      (node (ref "D4") (pin "1") (pinfunction "VDD_1") (pintype "bidirectional"))
      (node (ref "D5") (pin "1") (pinfunction "VDD_1") (pintype "bidirectional"))
      (node (ref "D6") (pin "1") (pinfunction "VDD_1") (pintype "bidirectional"))
      (node (ref "D7") (pin "1") (pinfunction "VDD_1") (pintype "bidirectional"))
      (node (ref "D8") (pin "1") (pinfunction "VDD_1") (pintype "bidirectional"))
      (node (ref "D9") (pin "1") (pinfunction "VDD_1") (pintype "bidirectional"))
      (node (ref "J2") (pin "2") (pinfunction "2_2") (pintype "passive"))
      (node (ref "R2") (pin "2") (pinfunction "2_2") (pintype "passive"))
      (node (ref "U2") (pin "8") (pinfunction "VCC_8") (pintype "bidirectional"))
    )
    (net (code "40") (name "unconnected-(D31-DO-Pad2)") (class "Default")
      (node (ref "D31") (pin "2") (pinfunction "DO_2") (pintype "bidirectional"))
    )
    (net (code "41") (name "unconnected-(X1-Pad2)") (class "Default")
      (node (ref "X1") (pin "2") (pinfunction "2_2") (pintype "passive"))
    )
    (net (code "42") (name "unconnected-(X1-Pad3)") (class "Default")
      (node (ref "X1") (pin "3") (pinfunction "3_3") (pintype "passive"))
    )
    (net (code "43") (name "unconnected-(X1-Pad5)") (class "Default")
      (node (ref "X1") (pin "5") (pinfunction "5_5") (pintype "passive"))
    )
  )
)
